# Connecors-Input.net
KiCad netlist of a schematic drawn in Altium Designer
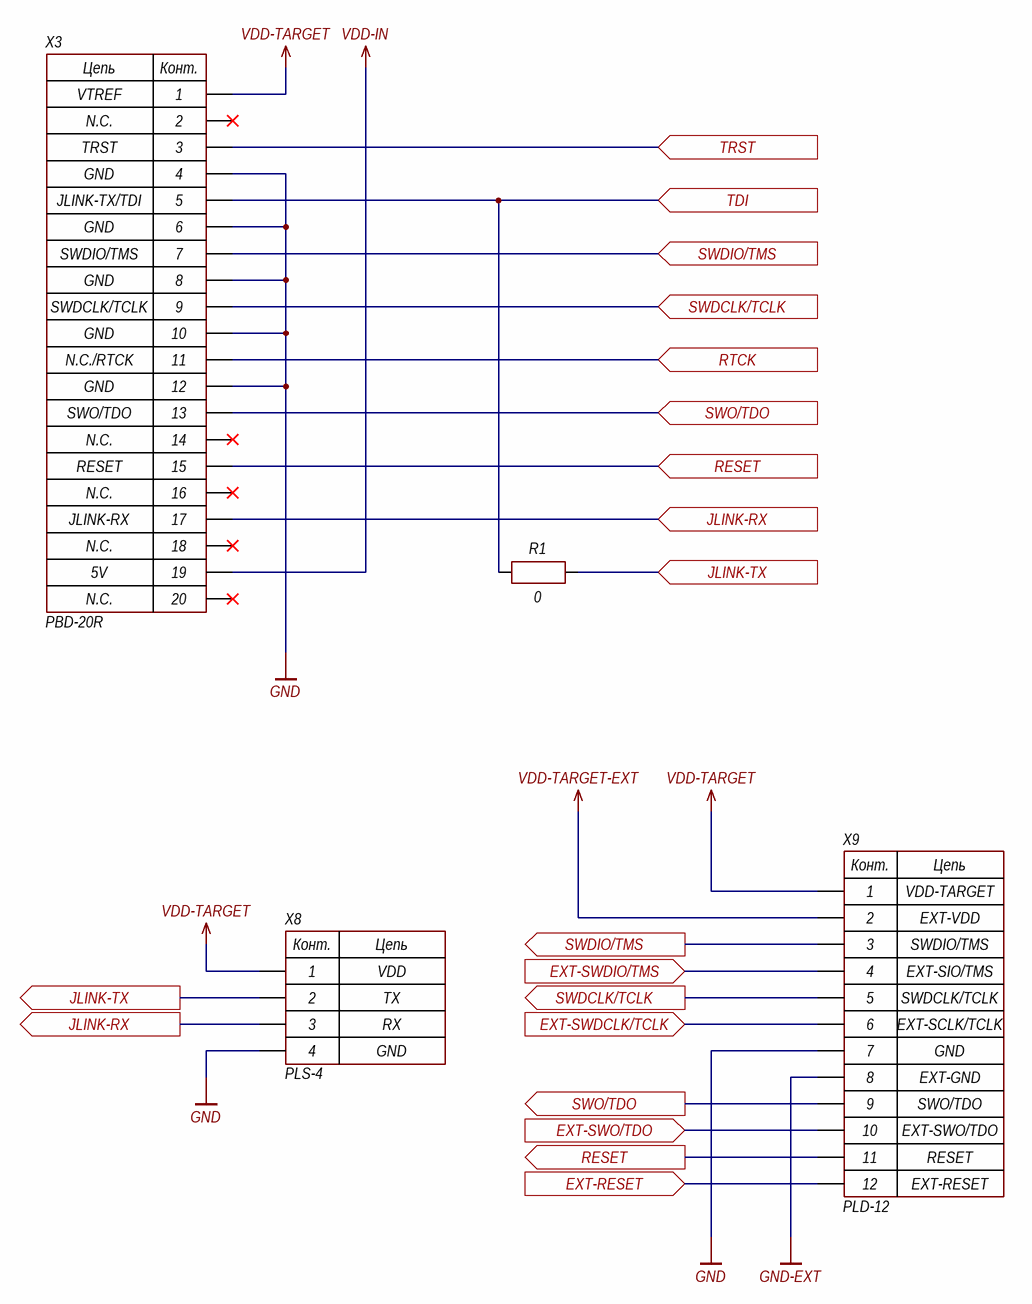
[diagram p0: Connecors-Input.SchDoc]

(export (version "E")
  (design (tool "Eeschema 10.0.6"))
  (components
    (comp (ref "R1") (value "0") (footprint "CH0402R") (libsource (lib "Discrete") (part "Resistor")))
    (comp (ref "X3")
      (value "PBD-20R")
      (footprint "CON: PBD-20R")
      (libsource (lib "Connectors") (part "20-Connector"))
    )
    (comp (ref "X8")
      (value "PLS-4")
      (footprint "CON: PLS-4")
      (libsource (lib "Connectors") (part "4-Connector"))
    )
    (comp (ref "X9")
      (value "PLD-12")
      (footprint "CON: PLD-12")
      (libsource (lib "Connectors") (part "12-Connector"))
    )
  )
  (nets
    (net (code "1") (name "/EXT-RESET") (class "Default")
      (node (ref "X9") (pin "12") (pinfunction "12_12") (pintype "passive"))
    )
    (net (code "2") (name "/EXT-SWDCLK{slash}TCLK") (class "Default")
      (node (ref "X9") (pin "6") (pinfunction "6_6") (pintype "passive"))
    )
    (net (code "3") (name "/EXT-SWDIO{slash}TMS") (class "Default")
      (node (ref "X9") (pin "4") (pinfunction "4_4") (pintype "passive"))
    )
    (net (code "4") (name "/EXT-SWO{slash}TDO") (class "Default")
      (node (ref "X9") (pin "10") (pinfunction "10_10") (pintype "passive"))
    )
    (net (code "5") (name "/JLINK-RX") (class "Default")
      (node (ref "X3") (pin "17") (pinfunction "17_17") (pintype "passive"))
      (node (ref "X8") (pin "3") (pinfunction "3_3") (pintype "passive"))
    )
    (net (code "6") (name "/JLINK-TX") (class "Default")
      (node (ref "R1") (pin "2") (pinfunction "2_2") (pintype "passive"))
      (node (ref "X8") (pin "2") (pinfunction "2_2") (pintype "passive"))
    )
    (net (code "7") (name "/RESET") (class "Default")
      (node (ref "X3") (pin "15") (pinfunction "15_15") (pintype "passive"))
      (node (ref "X9") (pin "11") (pinfunction "11_11") (pintype "passive"))
    )
    (net (code "8") (name "/RTCK") (class "Default")
      (node (ref "X3") (pin "11") (pinfunction "11_11") (pintype "passive"))
    )
    (net (code "9") (name "/SWDCLK{slash}TCLK") (class "Default")
      (node (ref "X3") (pin "9") (pinfunction "9_9") (pintype "passive"))
      (node (ref "X9") (pin "5") (pinfunction "5_5") (pintype "passive"))
    )
    (net (code "10") (name "/SWDIO{slash}TMS") (class "Default")
      (node (ref "X3") (pin "7") (pinfunction "7_7") (pintype "passive"))
      (node (ref "X9") (pin "3") (pinfunction "3_3") (pintype "passive"))
    )
    (net (code "11") (name "/SWO{slash}TDO") (class "Default")
      (node (ref "X3") (pin "13") (pinfunction "13_13") (pintype "passive"))
      (node (ref "X9") (pin "9") (pinfunction "9_9") (pintype "passive"))
    )
    (net (code "12") (name "/TDI") (class "Default")
      (node (ref "R1") (pin "1") (pinfunction "1_1") (pintype "passive"))
      (node (ref "X3") (pin "5") (pinfunction "5_5") (pintype "passive"))
    )
    (net (code "13") (name "/TRST") (class "Default")
      (node (ref "X3") (pin "3") (pinfunction "3_3") (pintype "passive"))
    )
    (net (code "14") (name "GND") (class "Default")
      (node (ref "X3") (pin "10") (pinfunction "10_10") (pintype "passive"))
      (node (ref "X3") (pin "12") (pinfunction "12_12") (pintype "passive"))
      (node (ref "X3") (pin "4") (pinfunction "4_4") (pintype "passive"))
      (node (ref "X3") (pin "6") (pinfunction "6_6") (pintype "passive"))
      (node (ref "X3") (pin "8") (pinfunction "8_8") (pintype "passive"))
      (node (ref "X8") (pin "4") (pinfunction "4_4") (pintype "passive"))
      (node (ref "X9") (pin "7") (pinfunction "7_7") (pintype "passive"))
    )
    (net (code "15") (name "GND-EXT") (class "Default")
      (node (ref "X9") (pin "8") (pinfunction "8_8") (pintype "passive"))
    )
    (net (code "16") (name "VDD-IN") (class "Default")
      (node (ref "X3") (pin "19") (pinfunction "19_19") (pintype "passive"))
    )
    (net (code "17") (name "VDD-TARGET") (class "Default")
      (node (ref "X3") (pin "1") (pinfunction "1_1") (pintype "passive"))
      (node (ref "X8") (pin "1") (pinfunction "1_1") (pintype "passive"))
      (node (ref "X9") (pin "1") (pinfunction "1_1") (pintype "passive"))
    )
    (net (code "18") (name "VDD-TARGET-EXT") (class "Default")
      (node (ref "X9") (pin "2") (pinfunction "2_2") (pintype "passive"))
    )
    (net (code "19") (name "unconnected-(X3-Pad2)") (class "Default")
      (node (ref "X3") (pin "2") (pinfunction "2_2") (pintype "passive+no_connect"))
    )
    (net (code "20") (name "unconnected-(X3-Pad14)") (class "Default")
      (node (ref "X3") (pin "14") (pinfunction "14_14") (pintype "passive+no_connect"))
    )
    (net (code "21") (name "unconnected-(X3-Pad16)") (class "Default")
      (node (ref "X3") (pin "16") (pinfunction "16_16") (pintype "passive+no_connect"))
    )
    (net (code "22") (name "unconnected-(X3-Pad18)") (class "Default")
      (node (ref "X3") (pin "18") (pinfunction "18_18") (pintype "passive+no_connect"))
    )
    (net (code "23") (name "unconnected-(X3-Pad20)") (class "Default")
      (node (ref "X3") (pin "20") (pinfunction "20_20") (pintype "passive+no_connect"))
    )
  )
)
